# ESP32_Microcontroller.net
KiCad netlist of a schematic drawn in Altium Designer
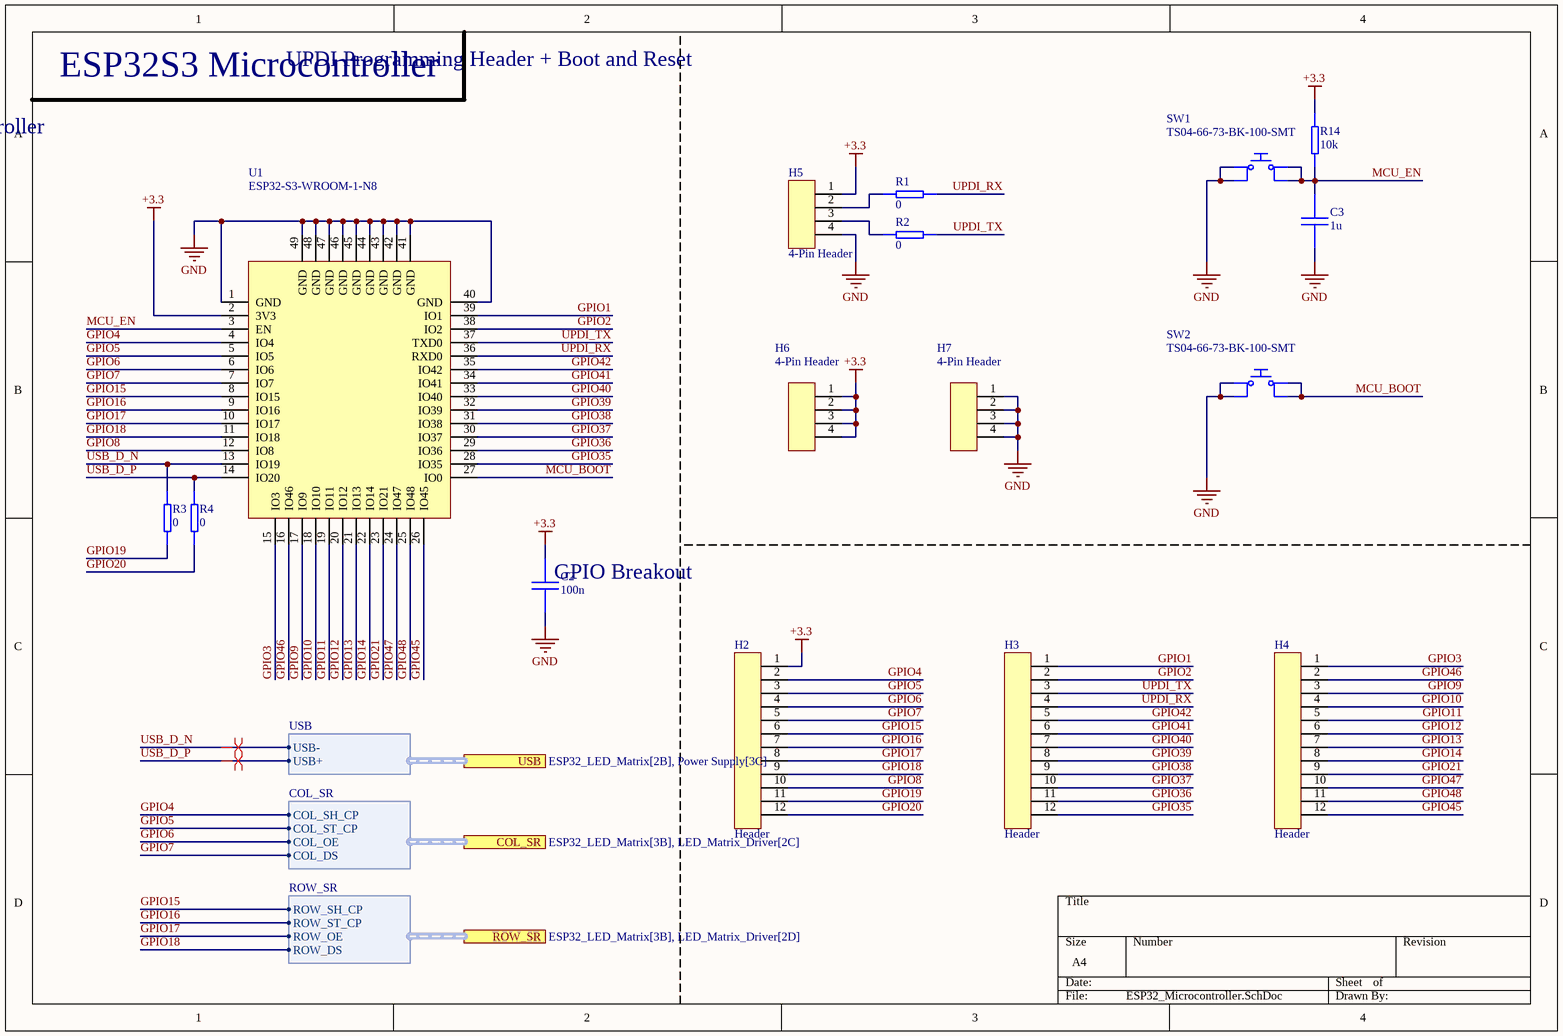
[diagram p0: ESP32_Microcontroller.SchDoc]

(export (version "E")
  (design (tool "Eeschema 10.0.6"))
  (components
    (comp (ref "C2")
      (value "100n")
      (footprint "IEEE_Workshop_Footprints:CAP0805")
      (description "Non Polarized Capacitor")
      (libsource (lib "HT2.2") (part "Capacitor - Non Polarized"))
    )
    (comp (ref "C3")
      (value "1u")
      (footprint "IEEE_Workshop_Footprints:CAP0805")
      (description "Non Polarized Capacitor")
      (libsource (lib "HT2.2") (part "Capacitor - Non Polarized"))
    )
    (comp (ref "H2")
      (value "Header")
      (footprint "IEEE_Workshop_Footprints:Header_1X12")
      (description "12-Pin Header")
      (libsource (lib "TD") (part "12-Pin Header"))
    )
    (comp (ref "H3")
      (value "Header")
      (footprint "IEEE_Workshop_Footprints:Header_1X12")
      (description "12-Pin Header")
      (libsource (lib "TD") (part "12-Pin Header"))
    )
    (comp (ref "H4")
      (value "Header")
      (footprint "IEEE_Workshop_Footprints:Header_1X12")
      (description "12-Pin Header")
      (libsource (lib "TD") (part "12-Pin Header"))
    )
    (comp (ref "H5")
      (value "4-Pin Header")
      (footprint "IEEE_Workshop_Footprints:Header_1X4")
      (libsource (lib "TD") (part "4-Pin Header"))
    )
    (comp (ref "H6")
      (value "4-Pin Header")
      (footprint "IEEE_Workshop_Footprints:Header_1X4")
      (libsource (lib "TD") (part "4-Pin Header"))
    )
    (comp (ref "H7")
      (value "4-Pin Header")
      (footprint "IEEE_Workshop_Footprints:Header_1X4")
      (libsource (lib "TD") (part "4-Pin Header"))
    )
    (comp (ref "R1")
      (value "0")
      (footprint "IEEE_Workshop_Footprints:RESC0805")
      (description "Resistor")
      (libsource (lib "TD") (part "Resistor"))
    )
    (comp (ref "R2")
      (value "0")
      (footprint "IEEE_Workshop_Footprints:RESC0805")
      (description "Resistor")
      (libsource (lib "TD") (part "Resistor"))
    )
    (comp (ref "R3")
      (value "0")
      (footprint "IEEE_Workshop_Footprints:RESC0805")
      (description "Resistor")
      (libsource (lib "TD") (part "Resistor"))
    )
    (comp (ref "R4")
      (value "0")
      (footprint "IEEE_Workshop_Footprints:RESC0805")
      (description "Resistor")
      (libsource (lib "TD") (part "Resistor"))
    )
    (comp (ref "R14")
      (value "10k")
      (footprint "IEEE_Workshop_Footprints:RESC0805")
      (description "Resistor")
      (libsource (lib "TD") (part "Resistor"))
    )
    (comp (ref "SW1")
      (value "TS04-66-73-BK-100-SMT")
      (footprint "IEEE_Workshop_Footprints:Tactile Button 6.0mm x 6.0mm")
      (description "Switch")
      (fields (field (name "MOUSER PART NUMBER") "179-TS046673BK100SMT"))
      (libsource (lib "TD") (part "TS04-66-73-BK-100-SMT"))
    )
    (comp (ref "SW2")
      (value "TS04-66-73-BK-100-SMT")
      (footprint "IEEE_Workshop_Footprints:Tactile Button 6.0mm x 6.0mm")
      (description "Switch")
      (fields (field (name "MOUSER PART NUMBER") "179-TS046673BK100SMT"))
      (libsource (lib "TD") (part "TS04-66-73-BK-100-SMT"))
    )
    (comp (ref "U1")
      (value "ESP32-S3-WROOM-1-N8")
      (footprint "IEEE_Workshop_Footprints:ESP32-S3-WROOM-1-N8")
      (description "ESP32 Microcontroller with Bluetooth and Wifi")
      (libsource (lib "HT2.3") (part "ESP32-S3-WROOM-1-N8"))
    )
  )
  (nets
    (net (code "4") (name "+3.3") (class "Default")
      (node (ref "C2") (pin "1") (pintype "passive"))
      (node (ref "H2") (pin "1") (pintype "passive"))
      (node (ref "H5") (pin "1") (pintype "passive"))
      (node (ref "H6") (pin "1") (pintype "passive"))
      (node (ref "H6") (pin "2") (pintype "passive"))
      (node (ref "H6") (pin "3") (pintype "passive"))
      (node (ref "H6") (pin "4") (pintype "passive"))
      (node (ref "R14") (pin "1") (pintype "passive"))
      (node (ref "U1") (pin "2") (pinfunction "3V3_2") (pintype "passive"))
    )
    (net (code "5") (name "/GPIO1") (class "Default")
      (node (ref "H3") (pin "1") (pintype "passive"))
      (node (ref "U1") (pin "39") (pinfunction "IO1_39") (pintype "passive"))
    )
    (net (code "6") (name "/GPIO2") (class "Default")
      (node (ref "H3") (pin "2") (pintype "passive"))
      (node (ref "U1") (pin "38") (pinfunction "IO2_38") (pintype "passive"))
    )
    (net (code "7") (name "/GPIO3") (class "Default")
      (node (ref "H4") (pin "1") (pintype "passive"))
      (node (ref "U1") (pin "15") (pinfunction "IO3_15") (pintype "passive"))
    )
    (net (code "8") (name "/GPIO4") (class "Default")
      (node (ref "H2") (pin "2") (pintype "passive"))
      (node (ref "U1") (pin "4") (pinfunction "IO4_4") (pintype "passive"))
    )
    (net (code "9") (name "/GPIO5") (class "Default")
      (node (ref "H2") (pin "3") (pintype "passive"))
      (node (ref "U1") (pin "5") (pinfunction "IO5_5") (pintype "passive"))
    )
    (net (code "10") (name "/GPIO6") (class "Default")
      (node (ref "H2") (pin "4") (pintype "passive"))
      (node (ref "U1") (pin "6") (pinfunction "IO6_6") (pintype "passive"))
    )
    (net (code "11") (name "/GPIO7") (class "Default")
      (node (ref "H2") (pin "5") (pintype "passive"))
      (node (ref "U1") (pin "7") (pinfunction "IO7_7") (pintype "passive"))
    )
    (net (code "12") (name "/GPIO8") (class "Default")
      (node (ref "H2") (pin "10") (pintype "passive"))
      (node (ref "U1") (pin "12") (pinfunction "IO8_12") (pintype "passive"))
    )
    (net (code "13") (name "/GPIO9") (class "Default")
      (node (ref "H4") (pin "3") (pintype "passive"))
      (node (ref "U1") (pin "17") (pinfunction "IO9_17") (pintype "passive"))
    )
    (net (code "14") (name "/GPIO10") (class "Default")
      (node (ref "H4") (pin "4") (pintype "passive"))
      (node (ref "U1") (pin "18") (pinfunction "IO10_18") (pintype "passive"))
    )
    (net (code "15") (name "/GPIO11") (class "Default")
      (node (ref "H4") (pin "5") (pintype "passive"))
      (node (ref "U1") (pin "19") (pinfunction "IO11_19") (pintype "passive"))
    )
    (net (code "16") (name "/GPIO12") (class "Default")
      (node (ref "H4") (pin "6") (pintype "passive"))
      (node (ref "U1") (pin "20") (pinfunction "IO12_20") (pintype "passive"))
    )
    (net (code "17") (name "/GPIO13") (class "Default")
      (node (ref "H4") (pin "7") (pintype "passive"))
      (node (ref "U1") (pin "21") (pinfunction "IO13_21") (pintype "passive"))
    )
    (net (code "18") (name "/GPIO14") (class "Default")
      (node (ref "H4") (pin "8") (pintype "passive"))
      (node (ref "U1") (pin "22") (pinfunction "IO14_22") (pintype "passive"))
    )
    (net (code "19") (name "/GPIO15") (class "Default")
      (node (ref "H2") (pin "6") (pintype "passive"))
      (node (ref "U1") (pin "8") (pinfunction "IO15_8") (pintype "passive"))
    )
    (net (code "20") (name "/GPIO16") (class "Default")
      (node (ref "H2") (pin "7") (pintype "passive"))
      (node (ref "U1") (pin "9") (pinfunction "IO16_9") (pintype "passive"))
    )
    (net (code "21") (name "/GPIO17") (class "Default")
      (node (ref "H2") (pin "8") (pintype "passive"))
      (node (ref "U1") (pin "10") (pinfunction "IO17_10") (pintype "passive"))
    )
    (net (code "22") (name "/GPIO18") (class "Default")
      (node (ref "H2") (pin "9") (pintype "passive"))
      (node (ref "U1") (pin "11") (pinfunction "IO18_11") (pintype "passive"))
    )
    (net (code "23") (name "/GPIO19") (class "Default")
      (node (ref "H2") (pin "11") (pintype "passive"))
      (node (ref "R3") (pin "1") (pintype "passive"))
    )
    (net (code "24") (name "/GPIO20") (class "Default")
      (node (ref "H2") (pin "12") (pintype "passive"))
      (node (ref "R4") (pin "1") (pintype "passive"))
    )
    (net (code "25") (name "/GPIO21") (class "Default")
      (node (ref "H4") (pin "9") (pintype "passive"))
      (node (ref "U1") (pin "23") (pinfunction "IO21_23") (pintype "passive"))
    )
    (net (code "26") (name "/GPIO35") (class "Default")
      (node (ref "H3") (pin "12") (pintype "passive"))
      (node (ref "U1") (pin "28") (pinfunction "IO35_28") (pintype "passive"))
    )
    (net (code "27") (name "/GPIO36") (class "Default")
      (node (ref "H3") (pin "11") (pintype "passive"))
      (node (ref "U1") (pin "29") (pinfunction "IO36_29") (pintype "passive"))
    )
    (net (code "28") (name "/GPIO37") (class "Default")
      (node (ref "H3") (pin "10") (pintype "passive"))
      (node (ref "U1") (pin "30") (pinfunction "IO37_30") (pintype "passive"))
    )
    (net (code "29") (name "/GPIO38") (class "Default")
      (node (ref "H3") (pin "9") (pintype "passive"))
      (node (ref "U1") (pin "31") (pinfunction "IO38_31") (pintype "passive"))
    )
    (net (code "30") (name "/GPIO39") (class "Default")
      (node (ref "H3") (pin "8") (pintype "passive"))
      (node (ref "U1") (pin "32") (pinfunction "IO39_32") (pintype "passive"))
    )
    (net (code "31") (name "/GPIO40") (class "Default")
      (node (ref "H3") (pin "7") (pintype "passive"))
      (node (ref "U1") (pin "33") (pinfunction "IO40_33") (pintype "passive"))
    )
    (net (code "32") (name "/GPIO41") (class "Default")
      (node (ref "H3") (pin "6") (pintype "passive"))
      (node (ref "U1") (pin "34") (pinfunction "IO41_34") (pintype "passive"))
    )
    (net (code "33") (name "/GPIO42") (class "Default")
      (node (ref "H3") (pin "5") (pintype "passive"))
      (node (ref "U1") (pin "35") (pinfunction "IO42_35") (pintype "passive"))
    )
    (net (code "34") (name "/GPIO45") (class "Default")
      (node (ref "H4") (pin "12") (pintype "passive"))
      (node (ref "U1") (pin "26") (pinfunction "IO45_26") (pintype "passive"))
    )
    (net (code "35") (name "/GPIO46") (class "Default")
      (node (ref "H4") (pin "2") (pintype "passive"))
      (node (ref "U1") (pin "16") (pinfunction "IO46_16") (pintype "passive"))
    )
    (net (code "36") (name "/GPIO47") (class "Default")
      (node (ref "H4") (pin "10") (pintype "passive"))
      (node (ref "U1") (pin "24") (pinfunction "IO47_24") (pintype "passive"))
    )
    (net (code "37") (name "/GPIO48") (class "Default")
      (node (ref "H4") (pin "11") (pintype "passive"))
      (node (ref "U1") (pin "25") (pinfunction "IO48_25") (pintype "passive"))
    )
    (net (code "38") (name "/MCU_BOOT") (class "Default")
      (node (ref "SW2") (pin "3") (pintype "passive"))
      (node (ref "SW2") (pin "4") (pintype "passive"))
      (node (ref "U1") (pin "27") (pinfunction "IO0_27") (pintype "passive"))
    )
    (net (code "39") (name "/MCU_EN") (class "Default")
      (node (ref "C3") (pin "1") (pintype "passive"))
      (node (ref "R14") (pin "2") (pintype "passive"))
      (node (ref "SW1") (pin "3") (pintype "passive"))
      (node (ref "SW1") (pin "4") (pintype "passive"))
      (node (ref "U1") (pin "3") (pinfunction "EN_3") (pintype "passive"))
    )
    (net (code "40") (name "/UPDI_RX") (class "Default")
      (node (ref "H3") (pin "4") (pintype "passive"))
      (node (ref "R1") (pin "1") (pintype "passive"))
      (node (ref "U1") (pin "36") (pinfunction "RXD0_36") (pintype "passive"))
    )
    (net (code "41") (name "/UPDI_TX") (class "Default")
      (node (ref "H3") (pin "3") (pintype "passive"))
      (node (ref "R2") (pin "1") (pintype "passive"))
      (node (ref "U1") (pin "37") (pinfunction "TXD0_37") (pintype "passive"))
    )
    (net (code "42") (name "/USB_D_N") (class "Default")
      (node (ref "R3") (pin "2") (pintype "passive"))
      (node (ref "U1") (pin "13") (pinfunction "IO19_13") (pintype "passive"))
    )
    (net (code "43") (name "/USB_D_P") (class "Default")
      (node (ref "R4") (pin "2") (pintype "passive"))
      (node (ref "U1") (pin "14") (pinfunction "IO20_14") (pintype "passive"))
    )
    (net (code "47") (name "GND") (class "Default")
      (node (ref "C2") (pin "2") (pintype "passive"))
      (node (ref "C3") (pin "2") (pintype "passive"))
      (node (ref "H5") (pin "4") (pintype "passive"))
      (node (ref "H7") (pin "1") (pintype "passive"))
      (node (ref "H7") (pin "2") (pintype "passive"))
      (node (ref "H7") (pin "3") (pintype "passive"))
      (node (ref "H7") (pin "4") (pintype "passive"))
      (node (ref "SW1") (pin "1") (pintype "passive"))
      (node (ref "SW1") (pin "2") (pintype "passive"))
      (node (ref "SW2") (pin "1") (pintype "passive"))
      (node (ref "SW2") (pin "2") (pintype "passive"))
      (node (ref "U1") (pin "1") (pinfunction "GND_1") (pintype "passive"))
      (node (ref "U1") (pin "40") (pinfunction "GND_40") (pintype "passive"))
      (node (ref "U1") (pin "41") (pinfunction "GND_41") (pintype "passive"))
      (node (ref "U1") (pin "42") (pinfunction "GND_42") (pintype "passive"))
      (node (ref "U1") (pin "43") (pinfunction "GND_43") (pintype "passive"))
      (node (ref "U1") (pin "44") (pinfunction "GND_44") (pintype "passive"))
      (node (ref "U1") (pin "45") (pinfunction "GND_45") (pintype "passive"))
      (node (ref "U1") (pin "46") (pinfunction "GND_46") (pintype "passive"))
      (node (ref "U1") (pin "47") (pinfunction "GND_47") (pintype "passive"))
      (node (ref "U1") (pin "48") (pinfunction "GND_48") (pintype "passive"))
      (node (ref "U1") (pin "49") (pinfunction "GND_49") (pintype "passive"))
    )
    (net (code "48") (name "Net-(H5-Pad2)") (class "Default")
      (node (ref "H5") (pin "2") (pintype "passive"))
      (node (ref "R1") (pin "2") (pintype "passive"))
    )
    (net (code "49") (name "Net-(H5-Pad3)") (class "Default")
      (node (ref "H5") (pin "3") (pintype "passive"))
      (node (ref "R2") (pin "2") (pintype "passive"))
    )
  )
)
